# LED_Panel_Driver.net
KiCad netlist of a schematic drawn in EAGLE
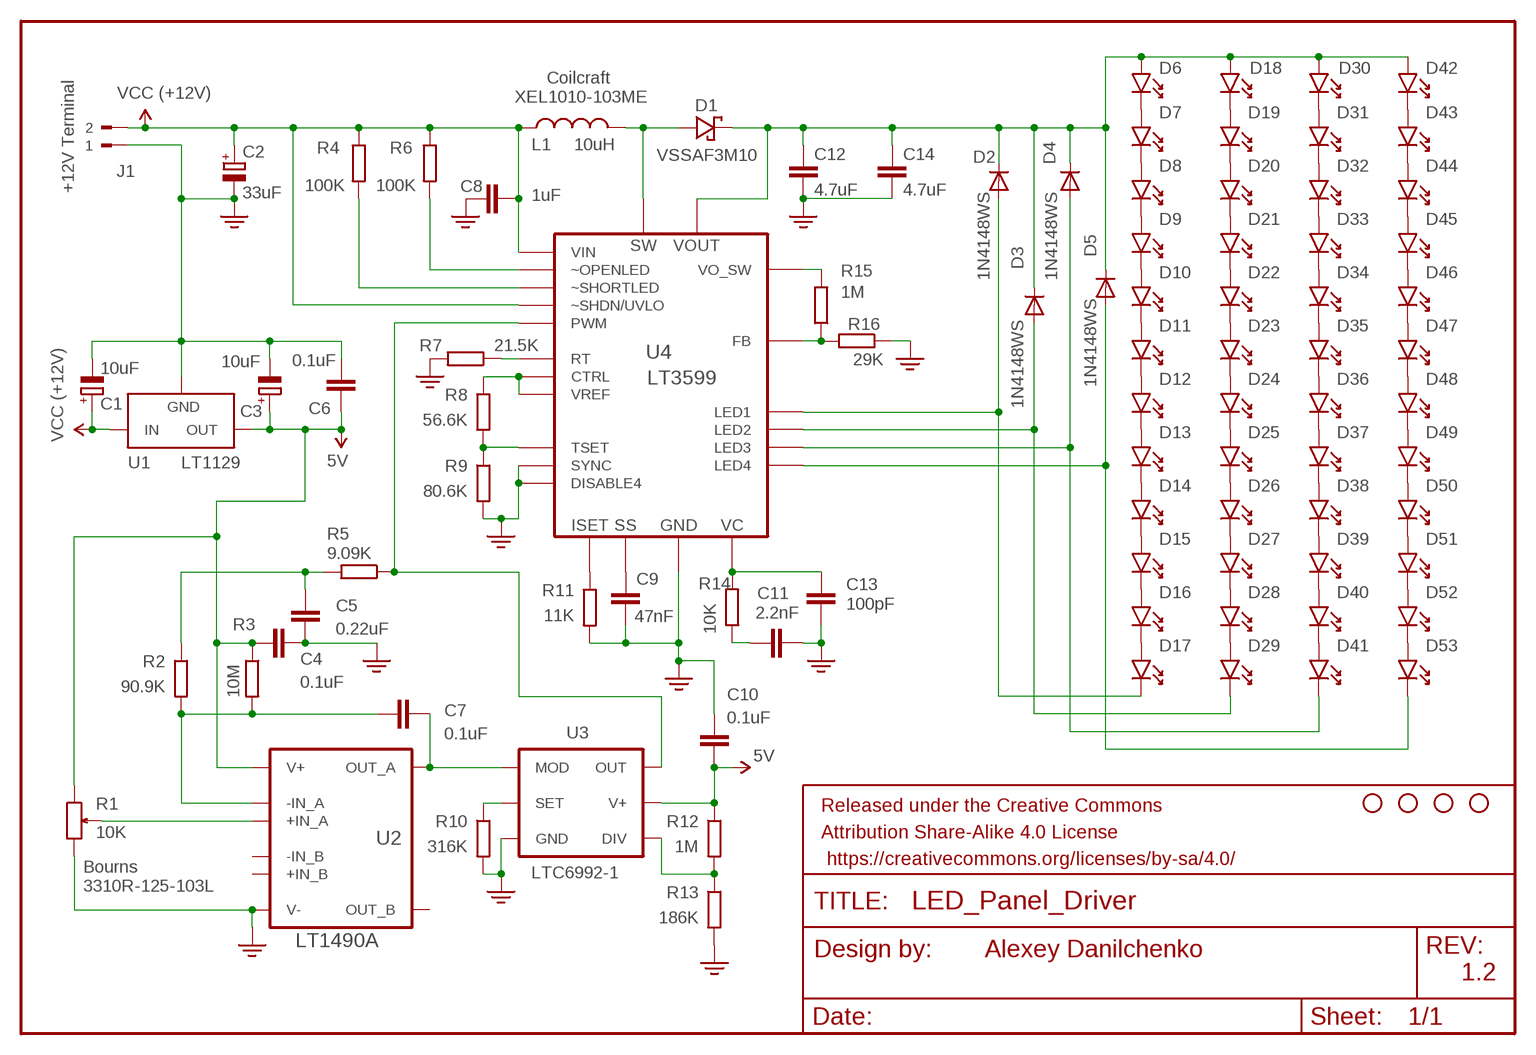
[diagram p0: schematic, sheet 1]

(export (version "E")
  (design (tool "Eeschema 10.0.6"))
  (components
    (comp (ref "C1")
      (value "10uF")
      (footprint "eagle-import:CT7343")
      (libsource (lib "eagle-import") (part "CPOL-EUCT7343"))
    )
    (comp (ref "C2")
      (value "33uF")
      (footprint "eagle-import:PANASONIC_E")
      (libsource (lib "eagle-import") (part "resistor_CPOL-EUE"))
    )
    (comp (ref "C3")
      (value "10uF")
      (footprint "eagle-import:CT7343")
      (libsource (lib "eagle-import") (part "CPOL-EUCT7343"))
    )
    (comp (ref "C4")
      (value "0.1uF")
      (footprint "eagle-import:C0805")
      (libsource (lib "eagle-import") (part "rcl_C-EUC0805"))
    )
    (comp (ref "C5")
      (value "0.22uF")
      (footprint "eagle-import:C0805")
      (libsource (lib "eagle-import") (part "rcl_C-EUC0805"))
    )
    (comp (ref "C6")
      (value "0.1uF")
      (footprint "eagle-import:C0805")
      (libsource (lib "eagle-import") (part "C-EUC0805"))
    )
    (comp (ref "C7")
      (value "0.1uF")
      (footprint "eagle-import:C0805")
      (libsource (lib "eagle-import") (part "rcl_C-EUC0805"))
    )
    (comp (ref "C8")
      (value "1uF")
      (footprint "eagle-import:C0805")
      (libsource (lib "eagle-import") (part "rcl_C-EUC0805"))
    )
    (comp (ref "C9")
      (value "47nF")
      (footprint "eagle-import:C0805")
      (libsource (lib "eagle-import") (part "rcl_C-EUC0805"))
    )
    (comp (ref "C10")
      (value "0.1uF")
      (footprint "eagle-import:C0805")
      (libsource (lib "eagle-import") (part "rcl_C-EUC0805"))
    )
    (comp (ref "C11")
      (value "2.2nF")
      (footprint "eagle-import:C0805")
      (libsource (lib "eagle-import") (part "rcl_C-EUC0805"))
    )
    (comp (ref "C12")
      (value "4.7uF")
      (footprint "eagle-import:C1812")
      (libsource (lib "eagle-import") (part "C-EUC1812"))
    )
    (comp (ref "C13")
      (value "100pF")
      (footprint "eagle-import:C0805")
      (libsource (lib "eagle-import") (part "rcl_C-EUC0805"))
    )
    (comp (ref "C14")
      (value "4.7uF")
      (footprint "eagle-import:C1812")
      (libsource (lib "eagle-import") (part "C-EUC1812"))
    )
    (comp (ref "D1")
      (value "VSSAF3M10")
      (footprint "eagle-import:SODFL5226X100N")
      (fields (field (name "ARROW_PART_NUMBER") "VSSAF3M10-M3/H"))
      (libsource (lib "eagle-import") (part "VSSAF3M10-M3_H"))
    )
    (comp (ref "D2")
      (value "1N4148WS")
      (footprint "eagle-import:SOD-323F")
      (libsource (lib "eagle-import") (part "DIODESOD-323F"))
    )
    (comp (ref "D3")
      (value "1N4148WS")
      (footprint "eagle-import:SOD-323F")
      (libsource (lib "eagle-import") (part "DIODESOD-323F"))
    )
    (comp (ref "D4")
      (value "1N4148WS")
      (footprint "eagle-import:SOD-323F")
      (libsource (lib "eagle-import") (part "DIODESOD-323F"))
    )
    (comp (ref "D5")
      (value "1N4148WS")
      (footprint "eagle-import:SOD-323F")
      (libsource (lib "eagle-import") (part "DIODESOD-323F"))
    )
    (comp (ref "D6")
      (value "YUJI_D50")
      (footprint "eagle-import:YUJI_D50")
      (libsource (lib "eagle-import") (part "YUJI_D50"))
    )
    (comp (ref "D7")
      (value "YUJI_D50")
      (footprint "eagle-import:YUJI_D50")
      (libsource (lib "eagle-import") (part "YUJI_D50"))
    )
    (comp (ref "D8")
      (value "YUJI_D50")
      (footprint "eagle-import:YUJI_D50")
      (libsource (lib "eagle-import") (part "YUJI_D50"))
    )
    (comp (ref "D9")
      (value "YUJI_D50")
      (footprint "eagle-import:YUJI_D50")
      (libsource (lib "eagle-import") (part "YUJI_D50"))
    )
    (comp (ref "D10")
      (value "YUJI_D50")
      (footprint "eagle-import:YUJI_D50")
      (libsource (lib "eagle-import") (part "YUJI_D50"))
    )
    (comp (ref "D11")
      (value "YUJI_D50")
      (footprint "eagle-import:YUJI_D50")
      (libsource (lib "eagle-import") (part "YUJI_D50"))
    )
    (comp (ref "D12")
      (value "YUJI_D50")
      (footprint "eagle-import:YUJI_D50")
      (libsource (lib "eagle-import") (part "YUJI_D50"))
    )
    (comp (ref "D13")
      (value "YUJI_D50")
      (footprint "eagle-import:YUJI_D50")
      (libsource (lib "eagle-import") (part "YUJI_D50"))
    )
    (comp (ref "D14")
      (value "YUJI_D50")
      (footprint "eagle-import:YUJI_D50")
      (libsource (lib "eagle-import") (part "YUJI_D50"))
    )
    (comp (ref "D15")
      (value "YUJI_D50")
      (footprint "eagle-import:YUJI_D50")
      (libsource (lib "eagle-import") (part "YUJI_D50"))
    )
    (comp (ref "D16")
      (value "YUJI_D50")
      (footprint "eagle-import:YUJI_D50")
      (libsource (lib "eagle-import") (part "YUJI_D50"))
    )
    (comp (ref "D17")
      (value "YUJI_D50")
      (footprint "eagle-import:YUJI_D50")
      (libsource (lib "eagle-import") (part "YUJI_D50"))
    )
    (comp (ref "D18")
      (value "YUJI_D50")
      (footprint "eagle-import:YUJI_D50")
      (libsource (lib "eagle-import") (part "YUJI_D50"))
    )
    (comp (ref "D19")
      (value "YUJI_D50")
      (footprint "eagle-import:YUJI_D50")
      (libsource (lib "eagle-import") (part "YUJI_D50"))
    )
    (comp (ref "D20")
      (value "YUJI_D50")
      (footprint "eagle-import:YUJI_D50")
      (libsource (lib "eagle-import") (part "YUJI_D50"))
    )
    (comp (ref "D21")
      (value "YUJI_D50")
      (footprint "eagle-import:YUJI_D50")
      (libsource (lib "eagle-import") (part "YUJI_D50"))
    )
    (comp (ref "D22")
      (value "YUJI_D50")
      (footprint "eagle-import:YUJI_D50")
      (libsource (lib "eagle-import") (part "YUJI_D50"))
    )
    (comp (ref "D23")
      (value "YUJI_D50")
      (footprint "eagle-import:YUJI_D50")
      (libsource (lib "eagle-import") (part "YUJI_D50"))
    )
    (comp (ref "D24")
      (value "YUJI_D50")
      (footprint "eagle-import:YUJI_D50")
      (libsource (lib "eagle-import") (part "YUJI_D50"))
    )
    (comp (ref "D25")
      (value "YUJI_D50")
      (footprint "eagle-import:YUJI_D50")
      (libsource (lib "eagle-import") (part "YUJI_D50"))
    )
    (comp (ref "D26")
      (value "YUJI_D50")
      (footprint "eagle-import:YUJI_D50")
      (libsource (lib "eagle-import") (part "YUJI_D50"))
    )
    (comp (ref "D27")
      (value "YUJI_D50")
      (footprint "eagle-import:YUJI_D50")
      (libsource (lib "eagle-import") (part "YUJI_D50"))
    )
    (comp (ref "D28")
      (value "YUJI_D50")
      (footprint "eagle-import:YUJI_D50")
      (libsource (lib "eagle-import") (part "YUJI_D50"))
    )
    (comp (ref "D29")
      (value "YUJI_D50")
      (footprint "eagle-import:YUJI_D50")
      (libsource (lib "eagle-import") (part "YUJI_D50"))
    )
    (comp (ref "D30")
      (value "YUJI_D50")
      (footprint "eagle-import:YUJI_D50")
      (libsource (lib "eagle-import") (part "YUJI_D50"))
    )
    (comp (ref "D31")
      (value "YUJI_D50")
      (footprint "eagle-import:YUJI_D50")
      (libsource (lib "eagle-import") (part "YUJI_D50"))
    )
    (comp (ref "D32")
      (value "YUJI_D50")
      (footprint "eagle-import:YUJI_D50")
      (libsource (lib "eagle-import") (part "YUJI_D50"))
    )
    (comp (ref "D33")
      (value "YUJI_D50")
      (footprint "eagle-import:YUJI_D50")
      (libsource (lib "eagle-import") (part "YUJI_D50"))
    )
    (comp (ref "D34")
      (value "YUJI_D50")
      (footprint "eagle-import:YUJI_D50")
      (libsource (lib "eagle-import") (part "YUJI_D50"))
    )
    (comp (ref "D35")
      (value "YUJI_D50")
      (footprint "eagle-import:YUJI_D50")
      (libsource (lib "eagle-import") (part "YUJI_D50"))
    )
    (comp (ref "D36")
      (value "YUJI_D50")
      (footprint "eagle-import:YUJI_D50")
      (libsource (lib "eagle-import") (part "YUJI_D50"))
    )
    (comp (ref "D37")
      (value "YUJI_D50")
      (footprint "eagle-import:YUJI_D50")
      (libsource (lib "eagle-import") (part "YUJI_D50"))
    )
    (comp (ref "D38")
      (value "YUJI_D50")
      (footprint "eagle-import:YUJI_D50")
      (libsource (lib "eagle-import") (part "YUJI_D50"))
    )
    (comp (ref "D39")
      (value "YUJI_D50")
      (footprint "eagle-import:YUJI_D50")
      (libsource (lib "eagle-import") (part "YUJI_D50"))
    )
    (comp (ref "D40")
      (value "YUJI_D50")
      (footprint "eagle-import:YUJI_D50")
      (libsource (lib "eagle-import") (part "YUJI_D50"))
    )
    (comp (ref "D41")
      (value "YUJI_D50")
      (footprint "eagle-import:YUJI_D50")
      (libsource (lib "eagle-import") (part "YUJI_D50"))
    )
    (comp (ref "D42")
      (value "YUJI_D50")
      (footprint "eagle-import:YUJI_D50")
      (libsource (lib "eagle-import") (part "YUJI_D50"))
    )
    (comp (ref "D43")
      (value "YUJI_D50")
      (footprint "eagle-import:YUJI_D50")
      (libsource (lib "eagle-import") (part "YUJI_D50"))
    )
    (comp (ref "D44")
      (value "YUJI_D50")
      (footprint "eagle-import:YUJI_D50")
      (libsource (lib "eagle-import") (part "YUJI_D50"))
    )
    (comp (ref "D45")
      (value "YUJI_D50")
      (footprint "eagle-import:YUJI_D50")
      (libsource (lib "eagle-import") (part "YUJI_D50"))
    )
    (comp (ref "D46")
      (value "YUJI_D50")
      (footprint "eagle-import:YUJI_D50")
      (libsource (lib "eagle-import") (part "YUJI_D50"))
    )
    (comp (ref "D47")
      (value "YUJI_D50")
      (footprint "eagle-import:YUJI_D50")
      (libsource (lib "eagle-import") (part "YUJI_D50"))
    )
    (comp (ref "D48")
      (value "YUJI_D50")
      (footprint "eagle-import:YUJI_D50")
      (libsource (lib "eagle-import") (part "YUJI_D50"))
    )
    (comp (ref "D49")
      (value "YUJI_D50")
      (footprint "eagle-import:YUJI_D50")
      (libsource (lib "eagle-import") (part "YUJI_D50"))
    )
    (comp (ref "D50")
      (value "YUJI_D50")
      (footprint "eagle-import:YUJI_D50")
      (libsource (lib "eagle-import") (part "YUJI_D50"))
    )
    (comp (ref "D51")
      (value "YUJI_D50")
      (footprint "eagle-import:YUJI_D50")
      (libsource (lib "eagle-import") (part "YUJI_D50"))
    )
    (comp (ref "D52")
      (value "YUJI_D50")
      (footprint "eagle-import:YUJI_D50")
      (libsource (lib "eagle-import") (part "YUJI_D50"))
    )
    (comp (ref "D53")
      (value "YUJI_D50")
      (footprint "eagle-import:YUJI_D50")
      (libsource (lib "eagle-import") (part "YUJI_D50"))
    )
    (comp (ref "FRAME1")
      (value "FRAME-LEDGER")
      (footprint "eagle-import:CREATIVE_COMMONS")
      (libsource (lib "eagle-import") (part "FRAME-LEDGER"))
    )
    (comp (ref "J1")
      (value "+12V Terminal")
      (footprint "eagle-import:WEIDMULLER_PM5.08_2")
      (fields (field (name "MPN") "PM5.08/2/90 BLK"))
      (libsource (lib "eagle-import") (part "PM5.08/2/90BLK"))
    )
    (comp (ref "L1")
      (value "10uH")
      (footprint "eagle-import:XAL1010")
      (libsource (lib "eagle-import") (part "XAL1010"))
    )
    (comp (ref "R1")
      (value "10K")
      (footprint "eagle-import:3310R125103L")
      (fields (field (name "ARROW_PART_NUMBER") "3310R-125-103L"))
      (libsource (lib "eagle-import") (part "3310R-125-103L"))
    )
    (comp (ref "R2")
      (value "90.9K")
      (footprint "eagle-import:R0805")
      (libsource (lib "eagle-import") (part "R-EU_R0805"))
    )
    (comp (ref "R3")
      (value "10M")
      (footprint "eagle-import:R0805")
      (libsource (lib "eagle-import") (part "R-EU_R0805"))
    )
    (comp (ref "R4")
      (value "100K")
      (footprint "eagle-import:R0805")
      (libsource (lib "eagle-import") (part "R-EU_R0805"))
    )
    (comp (ref "R5")
      (value "9.09K")
      (footprint "eagle-import:R0805")
      (libsource (lib "eagle-import") (part "R-EU_R0805"))
    )
    (comp (ref "R6")
      (value "100K")
      (footprint "eagle-import:R0805")
      (libsource (lib "eagle-import") (part "R-EU_R0805"))
    )
    (comp (ref "R7")
      (value "21.5K")
      (footprint "eagle-import:R0805")
      (libsource (lib "eagle-import") (part "R-EU_R0805"))
    )
    (comp (ref "R8")
      (value "56.6K")
      (footprint "eagle-import:R0805")
      (libsource (lib "eagle-import") (part "R-EU_R0805"))
    )
    (comp (ref "R9")
      (value "80.6K")
      (footprint "eagle-import:R0805")
      (libsource (lib "eagle-import") (part "R-EU_R0805"))
    )
    (comp (ref "R10")
      (value "316K")
      (footprint "eagle-import:R0805")
      (libsource (lib "eagle-import") (part "R-EU_R0805"))
    )
    (comp (ref "R11")
      (value "11K")
      (footprint "eagle-import:R0805")
      (libsource (lib "eagle-import") (part "R-EU_R0805"))
    )
    (comp (ref "R12")
      (value "1M")
      (footprint "eagle-import:R0805")
      (libsource (lib "eagle-import") (part "R-EU_R0805"))
    )
    (comp (ref "R13")
      (value "186K")
      (footprint "eagle-import:R0805")
      (libsource (lib "eagle-import") (part "R-EU_R0805"))
    )
    (comp (ref "R14")
      (value "10K")
      (footprint "eagle-import:R0805")
      (libsource (lib "eagle-import") (part "R-EU_R0805"))
    )
    (comp (ref "R15")
      (value "1M")
      (footprint "eagle-import:R0805")
      (libsource (lib "eagle-import") (part "R-EU_R0805"))
    )
    (comp (ref "R16")
      (value "29K")
      (footprint "eagle-import:R0805")
      (libsource (lib "eagle-import") (part "R-EU_R0805"))
    )
    (comp (ref "STANDOFF1")
      (value "STAND-OFF")
      (footprint "eagle-import:STAND-OFF")
      (libsource (lib "eagle-import") (part "STAND-OFF"))
    )
    (comp (ref "STANDOFF2")
      (value "STAND-OFF")
      (footprint "eagle-import:STAND-OFF")
      (libsource (lib "eagle-import") (part "STAND-OFF"))
    )
    (comp (ref "STANDOFF3")
      (value "STAND-OFF")
      (footprint "eagle-import:STAND-OFF")
      (libsource (lib "eagle-import") (part "STAND-OFF"))
    )
    (comp (ref "STANDOFF4")
      (value "STAND-OFF")
      (footprint "eagle-import:STAND-OFF")
      (libsource (lib "eagle-import") (part "STAND-OFF"))
    )
    (comp (ref "U1")
      (value "LT1129")
      (footprint "eagle-import:SOT223")
      (libsource (lib "eagle-import") (part "LT1129CST5"))
    )
    (comp (ref "U2")
      (value "LT1490A")
      (footprint "eagle-import:SOIC127P600X175-8N")
      (fields (field (name "MPN") "LT1490ACS8#PBF"))
      (libsource (lib "eagle-import") (part "LT1490ACS8PBF"))
    )
    (comp (ref "U3")
      (value "LTC6992-1")
      (footprint "eagle-import:SOT95P280X100-6N")
      (fields (field (name "MPN") "LTC6992CS6-1#TRPBF"))
      (libsource (lib "eagle-import") (part "LTC6992CS6-1TRPBF"))
    )
    (comp (ref "U4")
      (value "LT3599")
      (footprint "eagle-import:SOP65P640X120-29N")
      (fields (field (name "MPN") "LT3599EFE#PBF"))
      (libsource (lib "eagle-import") (part "LT3599EFEPBF"))
    )
  )
  (nets
    (net (code "1") (name "5V") (class "Default")
      (node (ref "C10") (pin "1") (pinfunction "1_1") (pintype "passive"))
      (node (ref "C3") (pin "+") (pinfunction "+_+") (pintype "passive"))
      (node (ref "C4") (pin "2") (pinfunction "2_2") (pintype "passive"))
      (node (ref "C6") (pin "1") (pinfunction "1_1") (pintype "passive"))
      (node (ref "R1") (pin "3") (pinfunction "CCW_3") (pintype "bidirectional"))
      (node (ref "R12") (pin "1") (pinfunction "1_1") (pintype "passive"))
      (node (ref "R3") (pin "1") (pinfunction "1_1") (pintype "passive"))
      (node (ref "U1") (pin "3") (pinfunction "OUT_3") (pintype "output"))
      (node (ref "U2") (pin "8") (pinfunction "V+_8") (pintype "power_in"))
      (node (ref "U3") (pin "5") (pinfunction "V+_5") (pintype "power_in"))
    )
    (net (code "2") (name "GND") (class "Default")
      (node (ref "C1") (pin "-") (pinfunction "-_-") (pintype "passive"))
      (node (ref "C10") (pin "2") (pinfunction "2_2") (pintype "passive"))
      (node (ref "C11") (pin "2") (pinfunction "2_2") (pintype "passive"))
      (node (ref "C12") (pin "2") (pinfunction "2_2") (pintype "passive"))
      (node (ref "C13") (pin "2") (pinfunction "2_2") (pintype "passive"))
      (node (ref "C14") (pin "2") (pinfunction "2_2") (pintype "passive"))
      (node (ref "C2") (pin "-") (pinfunction "-_-") (pintype "passive"))
      (node (ref "C3") (pin "-") (pinfunction "-_-") (pintype "passive"))
      (node (ref "C4") (pin "1") (pinfunction "1_1") (pintype "passive"))
      (node (ref "C5") (pin "1") (pinfunction "1_1") (pintype "passive"))
      (node (ref "C6") (pin "2") (pinfunction "2_2") (pintype "passive"))
      (node (ref "C8") (pin "2") (pinfunction "2_2") (pintype "passive"))
      (node (ref "C9") (pin "2") (pinfunction "2_2") (pintype "passive"))
      (node (ref "J1") (pin "1") (pinfunction "1_1") (pintype "passive"))
      (node (ref "R1") (pin "1") (pinfunction "CW_1") (pintype "bidirectional"))
      (node (ref "R10") (pin "2") (pinfunction "2_2") (pintype "passive"))
      (node (ref "R11") (pin "2") (pinfunction "2_2") (pintype "passive"))
      (node (ref "R13") (pin "2") (pinfunction "2_2") (pintype "passive"))
      (node (ref "R16") (pin "1") (pinfunction "1_1") (pintype "passive"))
      (node (ref "R7") (pin "2") (pinfunction "2_2") (pintype "passive"))
      (node (ref "R9") (pin "2") (pinfunction "2_2") (pintype "passive"))
      (node (ref "U1") (pin "2") (pinfunction "GND_2") (pintype "power_in"))
      (node (ref "U2") (pin "4") (pinfunction "V-_4") (pintype "power_in"))
      (node (ref "U3") (pin "2") (pinfunction "GND_2") (pintype "passive"))
      (node (ref "U4") (pin "19") (pinfunction "SYNC_19") (pintype "input"))
      (node (ref "U4") (pin "25") (pinfunction "GND_25") (pintype "passive"))
      (node (ref "U4") (pin "29") (pinfunction "GND_29") (pintype "passive"))
      (node (ref "U4") (pin "8") (pinfunction "DISABLE4_8") (pintype "input"))
    )
    (net (code "3") (name "Net-(C5-Pad2)") (class "Default")
      (node (ref "C5") (pin "2") (pinfunction "2_2") (pintype "passive"))
      (node (ref "R2") (pin "1") (pinfunction "1_1") (pintype "passive"))
      (node (ref "R5") (pin "2") (pinfunction "2_2") (pintype "passive"))
    )
    (net (code "4") (name "Net-(C11-Pad1)") (class "Default")
      (node (ref "C11") (pin "1") (pinfunction "1_1") (pintype "passive"))
      (node (ref "R14") (pin "1") (pinfunction "1_1") (pintype "passive"))
    )
    (net (code "5") (name "Net-(D1-A)") (class "Default")
      (node (ref "D1") (pin "2") (pinfunction "A_2") (pintype "bidirectional"))
      (node (ref "L1") (pin "2") (pinfunction "2_2") (pintype "passive"))
      (node (ref "U4") (pin "1") (pinfunction "SW_1") (pintype "output"))
    )
    (net (code "6") (name "Net-(D1-K)") (class "Default")
      (node (ref "C12") (pin "1") (pinfunction "1_1") (pintype "passive"))
      (node (ref "C14") (pin "1") (pinfunction "1_1") (pintype "passive"))
      (node (ref "D1") (pin "1") (pinfunction "K_1") (pintype "bidirectional"))
      (node (ref "D18") (pin "ANODE") (pinfunction "ANODE_ANODE") (pintype "bidirectional"))
      (node (ref "D2") (pin "C") (pinfunction "C_C") (pintype "passive"))
      (node (ref "D3") (pin "C") (pinfunction "C_C") (pintype "passive"))
      (node (ref "D30") (pin "ANODE") (pinfunction "ANODE_ANODE") (pintype "bidirectional"))
      (node (ref "D4") (pin "C") (pinfunction "C_C") (pintype "passive"))
      (node (ref "D42") (pin "ANODE") (pinfunction "ANODE_ANODE") (pintype "bidirectional"))
      (node (ref "D5") (pin "C") (pinfunction "C_C") (pintype "passive"))
      (node (ref "D6") (pin "ANODE") (pinfunction "ANODE_ANODE") (pintype "bidirectional"))
      (node (ref "U4") (pin "2") (pinfunction "VOUT_2") (pintype "output"))
    )
    (net (code "7") (name "Net-(D6-PadCATHODE)") (class "Default")
      (node (ref "D6") (pin "CATHODE") (pinfunction "CATHODE_CATHODE") (pintype "bidirectional"))
      (node (ref "D7") (pin "ANODE") (pinfunction "ANODE_ANODE") (pintype "bidirectional"))
    )
    (net (code "8") (name "Net-(D7-PadCATHODE)") (class "Default")
      (node (ref "D7") (pin "CATHODE") (pinfunction "CATHODE_CATHODE") (pintype "bidirectional"))
      (node (ref "D8") (pin "ANODE") (pinfunction "ANODE_ANODE") (pintype "bidirectional"))
    )
    (net (code "9") (name "Net-(D8-PadCATHODE)") (class "Default")
      (node (ref "D8") (pin "CATHODE") (pinfunction "CATHODE_CATHODE") (pintype "bidirectional"))
      (node (ref "D9") (pin "ANODE") (pinfunction "ANODE_ANODE") (pintype "bidirectional"))
    )
    (net (code "10") (name "Net-(D10-PadANODE)") (class "Default")
      (node (ref "D10") (pin "ANODE") (pinfunction "ANODE_ANODE") (pintype "bidirectional"))
      (node (ref "D9") (pin "CATHODE") (pinfunction "CATHODE_CATHODE") (pintype "bidirectional"))
    )
    (net (code "11") (name "Net-(D10-PadCATHODE)") (class "Default")
      (node (ref "D10") (pin "CATHODE") (pinfunction "CATHODE_CATHODE") (pintype "bidirectional"))
      (node (ref "D11") (pin "ANODE") (pinfunction "ANODE_ANODE") (pintype "bidirectional"))
    )
    (net (code "12") (name "Net-(D11-PadCATHODE)") (class "Default")
      (node (ref "D11") (pin "CATHODE") (pinfunction "CATHODE_CATHODE") (pintype "bidirectional"))
      (node (ref "D12") (pin "ANODE") (pinfunction "ANODE_ANODE") (pintype "bidirectional"))
    )
    (net (code "13") (name "Net-(D12-PadCATHODE)") (class "Default")
      (node (ref "D12") (pin "CATHODE") (pinfunction "CATHODE_CATHODE") (pintype "bidirectional"))
      (node (ref "D13") (pin "ANODE") (pinfunction "ANODE_ANODE") (pintype "bidirectional"))
    )
    (net (code "14") (name "Net-(D13-PadCATHODE)") (class "Default")
      (node (ref "D13") (pin "CATHODE") (pinfunction "CATHODE_CATHODE") (pintype "bidirectional"))
      (node (ref "D14") (pin "ANODE") (pinfunction "ANODE_ANODE") (pintype "bidirectional"))
    )
    (net (code "15") (name "Net-(D14-PadCATHODE)") (class "Default")
      (node (ref "D14") (pin "CATHODE") (pinfunction "CATHODE_CATHODE") (pintype "bidirectional"))
      (node (ref "D15") (pin "ANODE") (pinfunction "ANODE_ANODE") (pintype "bidirectional"))
    )
    (net (code "16") (name "Net-(D15-PadCATHODE)") (class "Default")
      (node (ref "D15") (pin "CATHODE") (pinfunction "CATHODE_CATHODE") (pintype "bidirectional"))
      (node (ref "D16") (pin "ANODE") (pinfunction "ANODE_ANODE") (pintype "bidirectional"))
    )
    (net (code "17") (name "Net-(D16-PadCATHODE)") (class "Default")
      (node (ref "D16") (pin "CATHODE") (pinfunction "CATHODE_CATHODE") (pintype "bidirectional"))
      (node (ref "D17") (pin "ANODE") (pinfunction "ANODE_ANODE") (pintype "bidirectional"))
    )
    (net (code "18") (name "Net-(D18-PadCATHODE)") (class "Default")
      (node (ref "D18") (pin "CATHODE") (pinfunction "CATHODE_CATHODE") (pintype "bidirectional"))
      (node (ref "D19") (pin "ANODE") (pinfunction "ANODE_ANODE") (pintype "bidirectional"))
    )
    (net (code "19") (name "Net-(D19-PadCATHODE)") (class "Default")
      (node (ref "D19") (pin "CATHODE") (pinfunction "CATHODE_CATHODE") (pintype "bidirectional"))
      (node (ref "D20") (pin "ANODE") (pinfunction "ANODE_ANODE") (pintype "bidirectional"))
    )
    (net (code "20") (name "Net-(D20-PadCATHODE)") (class "Default")
      (node (ref "D20") (pin "CATHODE") (pinfunction "CATHODE_CATHODE") (pintype "bidirectional"))
      (node (ref "D21") (pin "ANODE") (pinfunction "ANODE_ANODE") (pintype "bidirectional"))
    )
    (net (code "21") (name "Net-(D21-PadCATHODE)") (class "Default")
      (node (ref "D21") (pin "CATHODE") (pinfunction "CATHODE_CATHODE") (pintype "bidirectional"))
      (node (ref "D22") (pin "ANODE") (pinfunction "ANODE_ANODE") (pintype "bidirectional"))
    )
    (net (code "22") (name "Net-(D22-PadCATHODE)") (class "Default")
      (node (ref "D22") (pin "CATHODE") (pinfunction "CATHODE_CATHODE") (pintype "bidirectional"))
      (node (ref "D23") (pin "ANODE") (pinfunction "ANODE_ANODE") (pintype "bidirectional"))
    )
    (net (code "23") (name "Net-(D23-PadCATHODE)") (class "Default")
      (node (ref "D23") (pin "CATHODE") (pinfunction "CATHODE_CATHODE") (pintype "bidirectional"))
      (node (ref "D24") (pin "ANODE") (pinfunction "ANODE_ANODE") (pintype "bidirectional"))
    )
    (net (code "24") (name "Net-(D24-PadCATHODE)") (class "Default")
      (node (ref "D24") (pin "CATHODE") (pinfunction "CATHODE_CATHODE") (pintype "bidirectional"))
      (node (ref "D25") (pin "ANODE") (pinfunction "ANODE_ANODE") (pintype "bidirectional"))
    )
    (net (code "25") (name "Net-(D25-PadCATHODE)") (class "Default")
      (node (ref "D25") (pin "CATHODE") (pinfunction "CATHODE_CATHODE") (pintype "bidirectional"))
      (node (ref "D26") (pin "ANODE") (pinfunction "ANODE_ANODE") (pintype "bidirectional"))
    )
    (net (code "26") (name "Net-(D26-PadCATHODE)") (class "Default")
      (node (ref "D26") (pin "CATHODE") (pinfunction "CATHODE_CATHODE") (pintype "bidirectional"))
      (node (ref "D27") (pin "ANODE") (pinfunction "ANODE_ANODE") (pintype "bidirectional"))
    )
    (net (code "27") (name "Net-(D27-PadCATHODE)") (class "Default")
      (node (ref "D27") (pin "CATHODE") (pinfunction "CATHODE_CATHODE") (pintype "bidirectional"))
      (node (ref "D28") (pin "ANODE") (pinfunction "ANODE_ANODE") (pintype "bidirectional"))
    )
    (net (code "28") (name "Net-(D28-PadCATHODE)") (class "Default")
      (node (ref "D28") (pin "CATHODE") (pinfunction "CATHODE_CATHODE") (pintype "bidirectional"))
      (node (ref "D29") (pin "ANODE") (pinfunction "ANODE_ANODE") (pintype "bidirectional"))
    )
    (net (code "29") (name "Net-(D30-PadCATHODE)") (class "Default")
      (node (ref "D30") (pin "CATHODE") (pinfunction "CATHODE_CATHODE") (pintype "bidirectional"))
      (node (ref "D31") (pin "ANODE") (pinfunction "ANODE_ANODE") (pintype "bidirectional"))
    )
    (net (code "30") (name "Net-(D31-PadCATHODE)") (class "Default")
      (node (ref "D31") (pin "CATHODE") (pinfunction "CATHODE_CATHODE") (pintype "bidirectional"))
      (node (ref "D32") (pin "ANODE") (pinfunction "ANODE_ANODE") (pintype "bidirectional"))
    )
    (net (code "31") (name "Net-(D32-PadCATHODE)") (class "Default")
      (node (ref "D32") (pin "CATHODE") (pinfunction "CATHODE_CATHODE") (pintype "bidirectional"))
      (node (ref "D33") (pin "ANODE") (pinfunction "ANODE_ANODE") (pintype "bidirectional"))
    )
    (net (code "32") (name "Net-(D33-PadCATHODE)") (class "Default")
      (node (ref "D33") (pin "CATHODE") (pinfunction "CATHODE_CATHODE") (pintype "bidirectional"))
      (node (ref "D34") (pin "ANODE") (pinfunction "ANODE_ANODE") (pintype "bidirectional"))
    )
    (net (code "33") (name "Net-(D34-PadCATHODE)") (class "Default")
      (node (ref "D34") (pin "CATHODE") (pinfunction "CATHODE_CATHODE") (pintype "bidirectional"))
      (node (ref "D35") (pin "ANODE") (pinfunction "ANODE_ANODE") (pintype "bidirectional"))
    )
    (net (code "34") (name "Net-(D35-PadCATHODE)") (class "Default")
      (node (ref "D35") (pin "CATHODE") (pinfunction "CATHODE_CATHODE") (pintype "bidirectional"))
      (node (ref "D36") (pin "ANODE") (pinfunction "ANODE_ANODE") (pintype "bidirectional"))
    )
    (net (code "35") (name "Net-(D36-PadCATHODE)") (class "Default")
      (node (ref "D36") (pin "CATHODE") (pinfunction "CATHODE_CATHODE") (pintype "bidirectional"))
      (node (ref "D37") (pin "ANODE") (pinfunction "ANODE_ANODE") (pintype "bidirectional"))
    )
    (net (code "36") (name "Net-(D37-PadCATHODE)") (class "Default")
      (node (ref "D37") (pin "CATHODE") (pinfunction "CATHODE_CATHODE") (pintype "bidirectional"))
      (node (ref "D38") (pin "ANODE") (pinfunction "ANODE_ANODE") (pintype "bidirectional"))
    )
    (net (code "37") (name "Net-(D38-PadCATHODE)") (class "Default")
      (node (ref "D38") (pin "CATHODE") (pinfunction "CATHODE_CATHODE") (pintype "bidirectional"))
      (node (ref "D39") (pin "ANODE") (pinfunction "ANODE_ANODE") (pintype "bidirectional"))
    )
    (net (code "38") (name "Net-(D39-PadCATHODE)") (class "Default")
      (node (ref "D39") (pin "CATHODE") (pinfunction "CATHODE_CATHODE") (pintype "bidirectional"))
      (node (ref "D40") (pin "ANODE") (pinfunction "ANODE_ANODE") (pintype "bidirectional"))
    )
    (net (code "39") (name "Net-(D40-PadCATHODE)") (class "Default")
      (node (ref "D40") (pin "CATHODE") (pinfunction "CATHODE_CATHODE") (pintype "bidirectional"))
      (node (ref "D41") (pin "ANODE") (pinfunction "ANODE_ANODE") (pintype "bidirectional"))
    )
    (net (code "40") (name "Net-(D42-PadCATHODE)") (class "Default")
      (node (ref "D42") (pin "CATHODE") (pinfunction "CATHODE_CATHODE") (pintype "bidirectional"))
      (node (ref "D43") (pin "ANODE") (pinfunction "ANODE_ANODE") (pintype "bidirectional"))
    )
    (net (code "41") (name "Net-(D43-PadCATHODE)") (class "Default")
      (node (ref "D43") (pin "CATHODE") (pinfunction "CATHODE_CATHODE") (pintype "bidirectional"))
      (node (ref "D44") (pin "ANODE") (pinfunction "ANODE_ANODE") (pintype "bidirectional"))
    )
    (net (code "42") (name "Net-(D44-PadCATHODE)") (class "Default")
      (node (ref "D44") (pin "CATHODE") (pinfunction "CATHODE_CATHODE") (pintype "bidirectional"))
      (node (ref "D45") (pin "ANODE") (pinfunction "ANODE_ANODE") (pintype "bidirectional"))
    )
    (net (code "43") (name "Net-(D45-PadCATHODE)") (class "Default")
      (node (ref "D45") (pin "CATHODE") (pinfunction "CATHODE_CATHODE") (pintype "bidirectional"))
      (node (ref "D46") (pin "ANODE") (pinfunction "ANODE_ANODE") (pintype "bidirectional"))
    )
    (net (code "44") (name "Net-(D46-PadCATHODE)") (class "Default")
      (node (ref "D46") (pin "CATHODE") (pinfunction "CATHODE_CATHODE") (pintype "bidirectional"))
      (node (ref "D47") (pin "ANODE") (pinfunction "ANODE_ANODE") (pintype "bidirectional"))
    )
    (net (code "45") (name "Net-(D47-PadCATHODE)") (class "Default")
      (node (ref "D47") (pin "CATHODE") (pinfunction "CATHODE_CATHODE") (pintype "bidirectional"))
      (node (ref "D48") (pin "ANODE") (pinfunction "ANODE_ANODE") (pintype "bidirectional"))
    )
    (net (code "46") (name "Net-(D48-PadCATHODE)") (class "Default")
      (node (ref "D48") (pin "CATHODE") (pinfunction "CATHODE_CATHODE") (pintype "bidirectional"))
      (node (ref "D49") (pin "ANODE") (pinfunction "ANODE_ANODE") (pintype "bidirectional"))
    )
    (net (code "47") (name "Net-(D49-PadCATHODE)") (class "Default")
      (node (ref "D49") (pin "CATHODE") (pinfunction "CATHODE_CATHODE") (pintype "bidirectional"))
      (node (ref "D50") (pin "ANODE") (pinfunction "ANODE_ANODE") (pintype "bidirectional"))
    )
    (net (code "48") (name "Net-(D50-PadCATHODE)") (class "Default")
      (node (ref "D50") (pin "CATHODE") (pinfunction "CATHODE_CATHODE") (pintype "bidirectional"))
      (node (ref "D51") (pin "ANODE") (pinfunction "ANODE_ANODE") (pintype "bidirectional"))
    )
    (net (code "49") (name "Net-(D51-PadCATHODE)") (class "Default")
      (node (ref "D51") (pin "CATHODE") (pinfunction "CATHODE_CATHODE") (pintype "bidirectional"))
      (node (ref "D52") (pin "ANODE") (pinfunction "ANODE_ANODE") (pintype "bidirectional"))
    )
    (net (code "50") (name "Net-(D52-PadCATHODE)") (class "Default")
      (node (ref "D52") (pin "CATHODE") (pinfunction "CATHODE_CATHODE") (pintype "bidirectional"))
      (node (ref "D53") (pin "ANODE") (pinfunction "ANODE_ANODE") (pintype "bidirectional"))
    )
    (net (code "51") (name "Net-(R1-WIPER)") (class "Default")
      (node (ref "R1") (pin "2") (pinfunction "WIPER_2") (pintype "bidirectional"))
      (node (ref "U2") (pin "3") (pinfunction "+IN_A_3") (pintype "input"))
    )
    (net (code "52") (name "Net-(U2--IN_A)") (class "Default")
      (node (ref "C7") (pin "2") (pinfunction "2_2") (pintype "passive"))
      (node (ref "R2") (pin "2") (pinfunction "2_2") (pintype "passive"))
      (node (ref "R3") (pin "2") (pinfunction "2_2") (pintype "passive"))
      (node (ref "U2") (pin "2") (pinfunction "-IN_A_2") (pintype "input"))
    )
    (net (code "53") (name "Net-(U2-OUT_A)") (class "Default")
      (node (ref "C7") (pin "1") (pinfunction "1_1") (pintype "passive"))
      (node (ref "U2") (pin "1") (pinfunction "OUT_A_1") (pintype "output"))
      (node (ref "U3") (pin "1") (pinfunction "MOD_1") (pintype "input"))
    )
    (net (code "54") (name "Net-(U3-DIV)") (class "Default")
      (node (ref "R12") (pin "2") (pinfunction "2_2") (pintype "passive"))
      (node (ref "R13") (pin "1") (pinfunction "1_1") (pintype "passive"))
      (node (ref "U3") (pin "4") (pinfunction "DIV_4") (pintype "input"))
    )
    (net (code "55") (name "Net-(U3-OUT)") (class "Default")
      (node (ref "R5") (pin "1") (pinfunction "1_1") (pintype "passive"))
      (node (ref "U3") (pin "6") (pinfunction "OUT_6") (pintype "output"))
      (node (ref "U4") (pin "21") (pinfunction "PWM_21") (pintype "input"))
    )
    (net (code "56") (name "Net-(U3-SET)") (class "Default")
      (node (ref "R10") (pin "1") (pinfunction "1_1") (pintype "passive"))
      (node (ref "U3") (pin "3") (pinfunction "SET_3") (pintype "input"))
    )
    (net (code "57") (name "Net-(U4-CTRL)") (class "Default")
      (node (ref "R8") (pin "1") (pinfunction "1_1") (pintype "passive"))
      (node (ref "U4") (pin "14") (pinfunction "CTRL_14") (pintype "input"))
      (node (ref "U4") (pin "24") (pinfunction "VREF_24") (pintype "input"))
    )
    (net (code "58") (name "Net-(U4-FB)") (class "Default")
      (node (ref "R15") (pin "1") (pinfunction "1_1") (pintype "passive"))
      (node (ref "R16") (pin "2") (pinfunction "2_2") (pintype "passive"))
      (node (ref "U4") (pin "16") (pinfunction "FB_16") (pintype "input"))
    )
    (net (code "59") (name "Net-(U4-ISET)") (class "Default")
      (node (ref "R11") (pin "1") (pinfunction "1_1") (pintype "passive"))
      (node (ref "U4") (pin "13") (pinfunction "ISET_13") (pintype "input"))
    )
    (net (code "60") (name "Net-(U4-LED1)") (class "Default")
      (node (ref "D17") (pin "CATHODE") (pinfunction "CATHODE_CATHODE") (pintype "bidirectional"))
      (node (ref "D2") (pin "A") (pinfunction "A_A") (pintype "passive"))
      (node (ref "U4") (pin "4") (pinfunction "LED1_4") (pintype "output"))
    )
    (net (code "61") (name "Net-(U4-LED2)") (class "Default")
      (node (ref "D29") (pin "CATHODE") (pinfunction "CATHODE_CATHODE") (pintype "bidirectional"))
      (node (ref "D3") (pin "A") (pinfunction "A_A") (pintype "passive"))
      (node (ref "U4") (pin "5") (pinfunction "LED2_5") (pintype "output"))
    )
    (net (code "62") (name "Net-(U4-LED3)") (class "Default")
      (node (ref "D4") (pin "A") (pinfunction "A_A") (pintype "passive"))
      (node (ref "D41") (pin "CATHODE") (pinfunction "CATHODE_CATHODE") (pintype "bidirectional"))
      (node (ref "U4") (pin "6") (pinfunction "LED3_6") (pintype "output"))
    )
    (net (code "63") (name "Net-(U4-LED4)") (class "Default")
      (node (ref "D5") (pin "A") (pinfunction "A_A") (pintype "passive"))
      (node (ref "D53") (pin "CATHODE") (pinfunction "CATHODE_CATHODE") (pintype "bidirectional"))
      (node (ref "U4") (pin "7") (pinfunction "LED4_7") (pintype "output"))
    )
    (net (code "64") (name "Net-(U4-RT)") (class "Default")
      (node (ref "R7") (pin "1") (pinfunction "1_1") (pintype "passive"))
      (node (ref "U4") (pin "22") (pinfunction "RT_22") (pintype "passive"))
    )
    (net (code "65") (name "Net-(U4-SS)") (class "Default")
      (node (ref "C9") (pin "1") (pinfunction "1_1") (pintype "passive"))
      (node (ref "U4") (pin "23") (pinfunction "SS_23") (pintype "input"))
    )
    (net (code "66") (name "Net-(U4-TSET)") (class "Default")
      (node (ref "R8") (pin "2") (pinfunction "2_2") (pintype "passive"))
      (node (ref "R9") (pin "1") (pinfunction "1_1") (pintype "passive"))
      (node (ref "U4") (pin "17") (pinfunction "TSET_17") (pintype "input"))
    )
    (net (code "67") (name "Net-(U4-VC)") (class "Default")
      (node (ref "C13") (pin "1") (pinfunction "1_1") (pintype "passive"))
      (node (ref "R14") (pin "2") (pinfunction "2_2") (pintype "passive"))
      (node (ref "U4") (pin "15") (pinfunction "VC_15") (pintype "output"))
    )
    (net (code "68") (name "Net-(U4-VO_SW)") (class "Default")
      (node (ref "R15") (pin "2") (pinfunction "2_2") (pintype "passive"))
      (node (ref "U4") (pin "3") (pinfunction "VO_SW_3") (pintype "input"))
    )
    (net (code "69") (name "Net-(U4-~{OPENLED})") (class "Default")
      (node (ref "R6") (pin "2") (pinfunction "2_2") (pintype "passive"))
      (node (ref "U4") (pin "11") (pinfunction "~{OPENLED}_11") (pintype "output"))
    )
    (net (code "70") (name "Net-(U4-~{SHORTLED})") (class "Default")
      (node (ref "R4") (pin "2") (pinfunction "2_2") (pintype "passive"))
      (node (ref "U4") (pin "9") (pinfunction "~{SHORTLED}_9") (pintype "output"))
    )
    (net (code "71") (name "VCC (+12V)") (class "Default")
      (node (ref "C1") (pin "+") (pinfunction "+_+") (pintype "passive"))
      (node (ref "C2") (pin "+") (pinfunction "+_+") (pintype "passive"))
      (node (ref "C8") (pin "1") (pinfunction "1_1") (pintype "passive"))
      (node (ref "J1") (pin "2") (pinfunction "2_2") (pintype "passive"))
      (node (ref "L1") (pin "1") (pinfunction "1_1") (pintype "passive"))
      (node (ref "R4") (pin "1") (pinfunction "1_1") (pintype "passive"))
      (node (ref "R6") (pin "1") (pinfunction "1_1") (pintype "passive"))
      (node (ref "U1") (pin "1") (pinfunction "IN_1") (pintype "input"))
      (node (ref "U4") (pin "27") (pinfunction "~{SHDN/UVLO}_27") (pintype "input"))
      (node (ref "U4") (pin "28") (pinfunction "VIN_28") (pintype "power_in"))
    )
    (net (code "72") (name "unconnected-(U2-+IN_B-Pad5)") (class "Default")
      (node (ref "U2") (pin "5") (pinfunction "+IN_B_5") (pintype "input"))
    )
    (net (code "73") (name "unconnected-(U2--IN_B-Pad6)") (class "Default")
      (node (ref "U2") (pin "6") (pinfunction "-IN_B_6") (pintype "input"))
    )
    (net (code "74") (name "unconnected-(U2-OUT_B-Pad7)") (class "Default")
      (node (ref "U2") (pin "7") (pinfunction "OUT_B_7") (pintype "output"))
    )
  )
)
